# ADC_8CH.net
KiCad netlist of a schematic drawn in Altium Designer
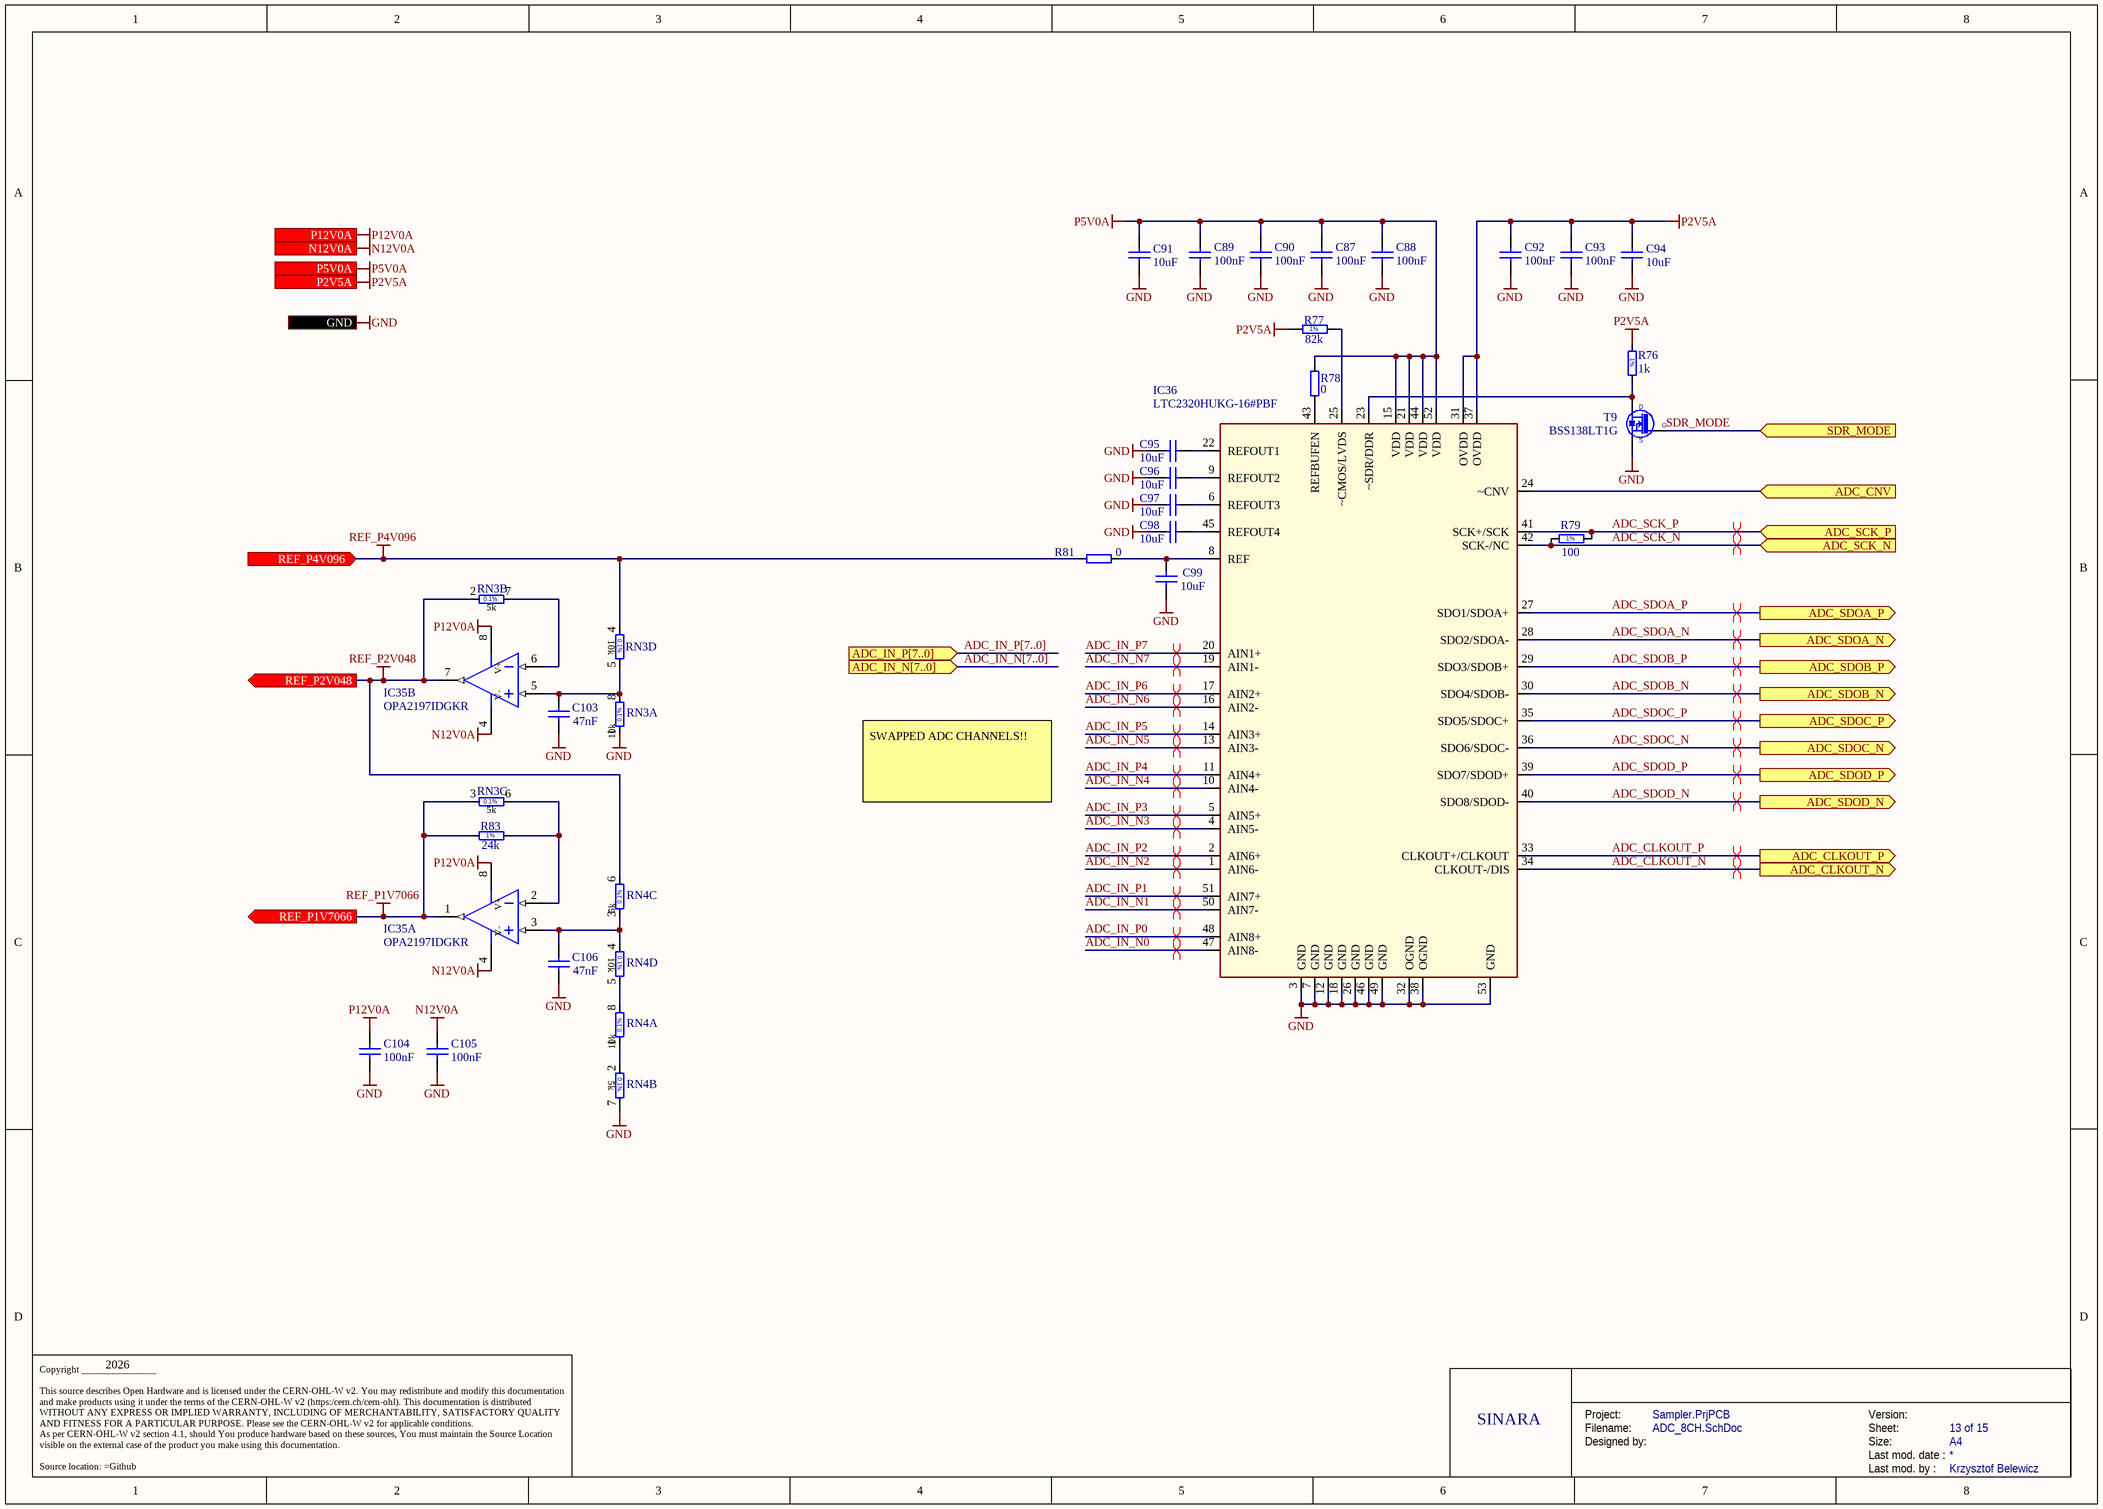
[diagram p0: ADC_8CH.SchDoc]

(export (version "E")
  (design (tool "Eeschema 10.0.6"))
  (components
    (comp (ref "C87")
      (value "100nF")
      (footprint "CAPC1005X55N")
      (description "Non-polarised capacitor")
      (fields
        (field (name "PART NUMBER") "CC0402_100NF_50V_10%_X7R")
        (field (name "VOLTAGE") "50V")
        (field (name "AUTHOR") "CERN DEM MR")
      )
      (libsource (lib "Capacitors") (part "Capacitor - non polarized"))
    )
    (comp (ref "C88")
      (value "100nF")
      (footprint "CAPC1005X55N")
      (description "Non-polarised capacitor")
      (fields
        (field (name "PART NUMBER") "CC0402_100NF_50V_10%_X7R")
        (field (name "VOLTAGE") "50V")
        (field (name "AUTHOR") "CERN DEM MR")
      )
      (libsource (lib "Capacitors") (part "Capacitor - non polarized"))
    )
    (comp (ref "C89")
      (value "100nF")
      (footprint "CAPC1005X55N")
      (description "Non-polarised capacitor")
      (fields
        (field (name "PART NUMBER") "CC0402_100NF_50V_10%_X7R")
        (field (name "VOLTAGE") "50V")
        (field (name "AUTHOR") "CERN DEM MR")
      )
      (libsource (lib "Capacitors") (part "Capacitor - non polarized"))
    )
    (comp (ref "C90")
      (value "100nF")
      (footprint "CAPC1005X55N")
      (description "Non-polarised capacitor")
      (fields
        (field (name "PART NUMBER") "CC0402_100NF_50V_10%_X7R")
        (field (name "VOLTAGE") "50V")
        (field (name "AUTHOR") "CERN DEM MR")
      )
      (libsource (lib "Capacitors") (part "Capacitor - non polarized"))
    )
    (comp (ref "C91")
      (value "10uF")
      (footprint "CAPC2012X95N")
      (description "Non-polarised capacitor")
      (fields
        (field (name "PART NUMBER") "CC0805_10UF_25V_10%_X5R")
        (field (name "VOLTAGE") "25V")
        (field (name "AUTHOR") "CERN DEM JLC")
      )
      (libsource (lib "Capacitors") (part "Capacitor - non polarized"))
    )
    (comp (ref "C92")
      (value "100nF")
      (footprint "CAPC1005X55N")
      (description "Non-polarised capacitor")
      (fields
        (field (name "PART NUMBER") "CC0402_100NF_50V_10%_X7R")
        (field (name "VOLTAGE") "50V")
        (field (name "AUTHOR") "CERN DEM MR")
      )
      (libsource (lib "Capacitors") (part "Capacitor - non polarized"))
    )
    (comp (ref "C93")
      (value "100nF")
      (footprint "CAPC1005X55N")
      (description "Non-polarised capacitor")
      (fields
        (field (name "PART NUMBER") "CC0402_100NF_50V_10%_X7R")
        (field (name "VOLTAGE") "50V")
        (field (name "AUTHOR") "CERN DEM MR")
      )
      (libsource (lib "Capacitors") (part "Capacitor - non polarized"))
    )
    (comp (ref "C94")
      (value "10uF")
      (footprint "CAPC2012X95N")
      (description "Non-polarised capacitor")
      (fields
        (field (name "PART NUMBER") "CC0805_10UF_25V_10%_X5R")
        (field (name "VOLTAGE") "25V")
        (field (name "AUTHOR") "CERN DEM JLC")
      )
      (libsource (lib "Capacitors") (part "Capacitor - non polarized"))
    )
    (comp (ref "C95")
      (value "10uF")
      (footprint "CAPC2012X95N")
      (description "Non-polarised capacitor")
      (fields
        (field (name "PART NUMBER") "CC0805_10UF_25V_10%_X5R")
        (field (name "VOLTAGE") "25V")
        (field (name "AUTHOR") "CERN DEM JLC")
      )
      (libsource (lib "Capacitors") (part "Capacitor - non polarized"))
    )
    (comp (ref "C96")
      (value "10uF")
      (footprint "CAPC2012X95N")
      (description "Non-polarised capacitor")
      (fields
        (field (name "PART NUMBER") "CC0805_10UF_25V_10%_X5R")
        (field (name "VOLTAGE") "25V")
        (field (name "AUTHOR") "CERN DEM JLC")
      )
      (libsource (lib "Capacitors") (part "Capacitor - non polarized"))
    )
    (comp (ref "C97")
      (value "10uF")
      (footprint "CAPC2012X95N")
      (description "Non-polarised capacitor")
      (fields
        (field (name "PART NUMBER") "CC0805_10UF_25V_10%_X5R")
        (field (name "VOLTAGE") "25V")
        (field (name "AUTHOR") "CERN DEM JLC")
      )
      (libsource (lib "Capacitors") (part "Capacitor - non polarized"))
    )
    (comp (ref "C98")
      (value "10uF")
      (footprint "CAPC2012X95N")
      (description "Non-polarised capacitor")
      (fields
        (field (name "PART NUMBER") "CC0805_10UF_25V_10%_X5R")
        (field (name "VOLTAGE") "25V")
        (field (name "AUTHOR") "CERN DEM JLC")
      )
      (libsource (lib "Capacitors") (part "Capacitor - non polarized"))
    )
    (comp (ref "C99")
      (value "10uF")
      (footprint "CAPC2012X95N")
      (description "Non-polarised capacitor")
      (fields
        (field (name "PART NUMBER") "CC0805_10UF_25V_10%_X5R")
        (field (name "VOLTAGE") "25V")
        (field (name "AUTHOR") "CERN DEM JLC")
      )
      (libsource (lib "Capacitors") (part "Capacitor - non polarized"))
    )
    (comp (ref "C103")
      (value "47nF")
      (footprint "CAPC2012X135N")
      (description "Non-polarised capacitor")
      (fields
        (field (name "PART NUMBER") "CC0805_47NF_25V_5%_C0G")
        (field (name "VOLTAGE") "25V")
        (field (name "AUTHOR") "CERN DEM JLC")
      )
      (libsource (lib "Capacitors") (part "Capacitor - non polarized"))
    )
    (comp (ref "C104")
      (value "100nF")
      (footprint "CAPC1005X55N")
      (description "Non-polarised capacitor")
      (fields
        (field (name "PART NUMBER") "CC0402_100NF_50V_10%_X7R")
        (field (name "VOLTAGE") "50V")
        (field (name "AUTHOR") "CERN DEM MR")
      )
      (libsource (lib "Capacitors") (part "Capacitor - non polarized"))
    )
    (comp (ref "C105")
      (value "100nF")
      (footprint "CAPC1005X55N")
      (description "Non-polarised capacitor")
      (fields
        (field (name "PART NUMBER") "CC0402_100NF_50V_10%_X7R")
        (field (name "VOLTAGE") "50V")
        (field (name "AUTHOR") "CERN DEM MR")
      )
      (libsource (lib "Capacitors") (part "Capacitor - non polarized"))
    )
    (comp (ref "C106")
      (value "47nF")
      (footprint "CAPC2012X135N")
      (description "Non-polarised capacitor")
      (fields
        (field (name "PART NUMBER") "CC0805_47NF_25V_5%_C0G")
        (field (name "VOLTAGE") "25V")
        (field (name "AUTHOR") "CERN DEM JLC")
      )
      (libsource (lib "Capacitors") (part "Capacitor - non polarized"))
    )
    (comp (ref "IC35")
      (value "OPA2197IDGKR")
      (footprint "SOP65P490X110-8N")
      (description "36-V, Precision, Rail-to-Rail Input Output, Low Offset Voltage Op Amp 8-VSSOP")
      (fields (field (name "MANUFACTURER") "TEXAS INSTRUMENTS") (field (name "AUTHOR") "GK"))
      (libsource (lib "LIBRARY_SCH") (part "OA_OPA2197IDGKR"))
    )
    (comp (ref "IC36")
      (value "LTC2320HUKG-16#PBF")
      (footprint "QFN50P700X800X80_HS-53M")
      (description "Octal, 16-Bit, 1.5Msps/Ch  Simultaneous Sampling ADC")
      (fields (field (name "MANUFACTURER") "LINEAR TECHNOLOGY") (field (name "AUTHOR") "GK"))
      (libsource (lib "LIBRARY_SCH") (part "ADC_LTC2320HUKG-16"))
    )
    (comp (ref "R76")
      (value "1k")
      (footprint "RESC1608X55N")
      (description "Resistor - 1%")
      (fields
        (field (name "PART NUMBER") "R0603_1K_1%_0.1W_100PPM")
        (field (name "POWER") "0.1W")
        (field (name "AUTHOR") "CERN DEM JLC")
      )
      (libsource (lib "Resistors") (part "Resistor - 1%"))
    )
    (comp (ref "R77")
      (value "82k")
      (footprint "RESC1608X55N")
      (description "Resistor - 1%")
      (fields
        (field (name "PART NUMBER") "R0603_82K_1%_0.1W_100PPM")
        (field (name "POWER") "0.1W")
        (field (name "AUTHOR") "CERN DEM JLC")
      )
      (libsource (lib "Resistors") (part "Resistor - 1%"))
    )
    (comp (ref "R78")
      (value "0")
      (footprint "RESC1005X40N")
      (description "Resistor")
      (fields
        (field (name "PART NUMBER") "R0402_0R_JUMPER")
        (field (name "MANUFACTURER") "GENERIC")
        (field (name "AUTHOR") "CERN DEM JLC")
      )
      (libsource (lib "Resistors") (part "Resistor"))
    )
    (comp (ref "R79")
      (value "100")
      (footprint "RESC1005X40N")
      (description "Resistor - 1%")
      (fields
        (field (name "PART NUMBER") "R0402_100R_1%_0.1W_100PPM")
        (field (name "POWER") "0.1W")
        (field (name "AUTHOR") "CERN DEM JLC")
      )
      (libsource (lib "Resistors") (part "Resistor - 1%"))
    )
    (comp (ref "R81")
      (value "0")
      (footprint "RESC1005X40N")
      (description "Resistor")
      (fields
        (field (name "PART NUMBER") "R0402_0R_JUMPER")
        (field (name "MANUFACTURER") "GENERIC")
        (field (name "AUTHOR") "CERN DEM JLC")
      )
      (libsource (lib "Resistors") (part "Resistor"))
    )
    (comp (ref "R83")
      (value "24k")
      (footprint "RESC1608X55N")
      (description "Resistor - 1%")
      (fields
        (field (name "PART NUMBER") "R0603_24K_1%_0.1W_100PPM")
        (field (name "POWER") "0.1W")
        (field (name "AUTHOR") "CERN DEM JLC")
      )
      (libsource (lib "Resistors") (part "Resistor - 1%"))
    )
    (comp (ref "RN3")
      (value "10k 5K 5K 10K")
      (footprint "SOIC127P600X175-8N")
      (description "DIL8 Resistor Network 4 Resistors 10k-5k-5k-10k 0.1%")
      (fields
        (field (name "PART NUMBER") "RN_10K_5K_VISHAY_AORN2-1AT3")
        (field (name "POWER") "4x0.1W")
        (field (name "AUTHOR") "CERN DEM JLC")
      )
      (libsource (lib "Resistors") (part "RN DIL8_4xR_10k-5k-5k-10k_0.1%"))
    )
    (comp (ref "RN4")
      (value "10k 5K 5K 10K")
      (footprint "SOIC127P600X175-8N")
      (description "DIL8 Resistor Network 4 Resistors 10k-5k-5k-10k 0.1%")
      (fields
        (field (name "PART NUMBER") "RN_10K_5K_VISHAY_AORN2-1AT3")
        (field (name "POWER") "4x0.1W")
        (field (name "AUTHOR") "CERN DEM JLC")
      )
      (libsource (lib "Resistors") (part "RN DIL8_4xR_10k-5k-5k-10k_0.1%"))
    )
    (comp (ref "T9")
      (value "BSS138LT1G")
      (footprint "SOT95P240X110-3N")
      (description "N-CHANNEL MOSFET WITH DIODE")
      (fields (field (name "MANUFACTURER") "ON SEMICONDUCTOR") (field (name "AUTHOR") "CERN DEM JLC"))
      (libsource (lib "ICs And Semiconductors") (part "N-MOSFET-D 1G 2S 3D"))
    )
  )
  (nets
    (net (code "1") (name "/ADC_CLKOUT_N") (class "Default")
      (node (ref "IC36") (pin "34") (pinfunction "CLKOUT-/DIS_34") (pintype "passive"))
    )
    (net (code "2") (name "/ADC_CLKOUT_P") (class "Default")
      (node (ref "IC36") (pin "33") (pinfunction "CLKOUT+/CLKOUT_33") (pintype "passive"))
    )
    (net (code "3") (name "/ADC_CNV") (class "Default")
      (node (ref "IC36") (pin "24") (pinfunction "~CNV_24") (pintype "passive"))
    )
    (net (code "4") (name "/ADC_IN_N0") (class "Default")
      (node (ref "IC36") (pin "47") (pinfunction "AIN8-_47") (pintype "passive"))
    )
    (net (code "5") (name "/ADC_IN_N1") (class "Default")
      (node (ref "IC36") (pin "50") (pinfunction "AIN7-_50") (pintype "passive"))
    )
    (net (code "6") (name "/ADC_IN_N2") (class "Default")
      (node (ref "IC36") (pin "1") (pinfunction "AIN6-_1") (pintype "passive"))
    )
    (net (code "7") (name "/ADC_IN_N3") (class "Default")
      (node (ref "IC36") (pin "4") (pinfunction "AIN5-_4") (pintype "passive"))
    )
    (net (code "8") (name "/ADC_IN_N4") (class "Default")
      (node (ref "IC36") (pin "10") (pinfunction "AIN4-_10") (pintype "passive"))
    )
    (net (code "9") (name "/ADC_IN_N5") (class "Default")
      (node (ref "IC36") (pin "13") (pinfunction "AIN3-_13") (pintype "passive"))
    )
    (net (code "10") (name "/ADC_IN_N6") (class "Default")
      (node (ref "IC36") (pin "16") (pinfunction "AIN2-_16") (pintype "passive"))
    )
    (net (code "11") (name "/ADC_IN_N7") (class "Default")
      (node (ref "IC36") (pin "19") (pinfunction "AIN1-_19") (pintype "passive"))
    )
    (net (code "13") (name "/ADC_IN_P0") (class "Default")
      (node (ref "IC36") (pin "48") (pinfunction "AIN8+_48") (pintype "passive"))
    )
    (net (code "14") (name "/ADC_IN_P1") (class "Default")
      (node (ref "IC36") (pin "51") (pinfunction "AIN7+_51") (pintype "passive"))
    )
    (net (code "15") (name "/ADC_IN_P2") (class "Default")
      (node (ref "IC36") (pin "2") (pinfunction "AIN6+_2") (pintype "passive"))
    )
    (net (code "16") (name "/ADC_IN_P3") (class "Default")
      (node (ref "IC36") (pin "5") (pinfunction "AIN5+_5") (pintype "passive"))
    )
    (net (code "17") (name "/ADC_IN_P4") (class "Default")
      (node (ref "IC36") (pin "11") (pinfunction "AIN4+_11") (pintype "passive"))
    )
    (net (code "18") (name "/ADC_IN_P5") (class "Default")
      (node (ref "IC36") (pin "14") (pinfunction "AIN3+_14") (pintype "passive"))
    )
    (net (code "19") (name "/ADC_IN_P6") (class "Default")
      (node (ref "IC36") (pin "17") (pinfunction "AIN2+_17") (pintype "passive"))
    )
    (net (code "20") (name "/ADC_IN_P7") (class "Default")
      (node (ref "IC36") (pin "20") (pinfunction "AIN1+_20") (pintype "passive"))
    )
    (net (code "22") (name "/ADC_SCK_N") (class "Default")
      (node (ref "IC36") (pin "42") (pinfunction "SCK-/NC_42") (pintype "passive"))
      (node (ref "R79") (pin "1") (pinfunction "1_1") (pintype "passive"))
    )
    (net (code "23") (name "/ADC_SCK_P") (class "Default")
      (node (ref "IC36") (pin "41") (pinfunction "SCK+/SCK_41") (pintype "passive"))
      (node (ref "R79") (pin "2") (pinfunction "2_2") (pintype "passive"))
    )
    (net (code "24") (name "/ADC_SDOA_N") (class "Default")
      (node (ref "IC36") (pin "28") (pinfunction "SDO2/SDOA-_28") (pintype "passive"))
    )
    (net (code "25") (name "/ADC_SDOA_P") (class "Default")
      (node (ref "IC36") (pin "27") (pinfunction "SDO1/SDOA+_27") (pintype "passive"))
    )
    (net (code "26") (name "/ADC_SDOB_N") (class "Default")
      (node (ref "IC36") (pin "30") (pinfunction "SDO4/SDOB-_30") (pintype "passive"))
    )
    (net (code "27") (name "/ADC_SDOB_P") (class "Default")
      (node (ref "IC36") (pin "29") (pinfunction "SDO3/SDOB+_29") (pintype "passive"))
    )
    (net (code "28") (name "/ADC_SDOC_N") (class "Default")
      (node (ref "IC36") (pin "36") (pinfunction "SDO6/SDOC-_36") (pintype "passive"))
    )
    (net (code "29") (name "/ADC_SDOC_P") (class "Default")
      (node (ref "IC36") (pin "35") (pinfunction "SDO5/SDOC+_35") (pintype "passive"))
    )
    (net (code "30") (name "/ADC_SDOD_N") (class "Default")
      (node (ref "IC36") (pin "40") (pinfunction "SDO8/SDOD-_40") (pintype "passive"))
    )
    (net (code "31") (name "/ADC_SDOD_P") (class "Default")
      (node (ref "IC36") (pin "39") (pinfunction "SDO7/SDOD+_39") (pintype "passive"))
    )
    (net (code "32") (name "/SDR_MODE") (class "Default")
      (node (ref "T9") (pin "1") (pinfunction "G_1") (pintype "passive"))
    )
    (net (code "33") (name "GND") (class "Default")
      (node (ref "C103") (pin "1") (pinfunction "1_1") (pintype "passive"))
      (node (ref "C104") (pin "1") (pinfunction "1_1") (pintype "passive"))
      (node (ref "C105") (pin "1") (pinfunction "1_1") (pintype "passive"))
      (node (ref "C106") (pin "1") (pinfunction "1_1") (pintype "passive"))
      (node (ref "C87") (pin "1") (pinfunction "1_1") (pintype "passive"))
      (node (ref "C88") (pin "1") (pinfunction "1_1") (pintype "passive"))
      (node (ref "C89") (pin "1") (pinfunction "1_1") (pintype "passive"))
      (node (ref "C90") (pin "1") (pinfunction "1_1") (pintype "passive"))
      (node (ref "C91") (pin "1") (pinfunction "1_1") (pintype "passive"))
      (node (ref "C92") (pin "1") (pinfunction "1_1") (pintype "passive"))
      (node (ref "C93") (pin "1") (pinfunction "1_1") (pintype "passive"))
      (node (ref "C94") (pin "1") (pinfunction "1_1") (pintype "passive"))
      (node (ref "C95") (pin "1") (pinfunction "1_1") (pintype "passive"))
      (node (ref "C96") (pin "1") (pinfunction "1_1") (pintype "passive"))
      (node (ref "C97") (pin "1") (pinfunction "1_1") (pintype "passive"))
      (node (ref "C98") (pin "1") (pinfunction "1_1") (pintype "passive"))
      (node (ref "C99") (pin "1") (pinfunction "1_1") (pintype "passive"))
      (node (ref "IC36") (pin "12") (pinfunction "GND_12") (pintype "passive"))
      (node (ref "IC36") (pin "18") (pinfunction "GND_18") (pintype "passive"))
      (node (ref "IC36") (pin "26") (pinfunction "GND_26") (pintype "passive"))
      (node (ref "IC36") (pin "3") (pinfunction "GND_3") (pintype "passive"))
      (node (ref "IC36") (pin "32") (pinfunction "OGND_32") (pintype "passive"))
      (node (ref "IC36") (pin "38") (pinfunction "OGND_38") (pintype "passive"))
      (node (ref "IC36") (pin "46") (pinfunction "GND_46") (pintype "passive"))
      (node (ref "IC36") (pin "49") (pinfunction "GND_49") (pintype "passive"))
      (node (ref "IC36") (pin "53") (pinfunction "GND_53") (pintype "passive"))
      (node (ref "IC36") (pin "7") (pinfunction "GND_7") (pintype "passive"))
      (node (ref "RN3") (pin "1") (pinfunction "1_1") (pintype "passive"))
      (node (ref "RN4") (pin "7") (pinfunction "7_7") (pintype "passive"))
      (node (ref "T9") (pin "2") (pinfunction "S_2") (pintype "passive"))
    )
    (net (code "34") (name "N12V0A") (class "Default")
      (node (ref "C105") (pin "2") (pinfunction "2_2") (pintype "passive"))
      (node (ref "IC35") (pin "4") (pinfunction "V-_4") (pintype "power_in"))
    )
    (net (code "35") (name "Net-(IC35A-IN+)") (class "Default")
      (node (ref "C106") (pin "2") (pinfunction "2_2") (pintype "passive"))
      (node (ref "IC35") (pin "3") (pinfunction "IN+_3") (pintype "input"))
      (node (ref "RN4") (pin "3") (pinfunction "3_3") (pintype "passive"))
      (node (ref "RN4") (pin "4") (pinfunction "4_4") (pintype "passive"))
    )
    (net (code "36") (name "Net-(IC35A-IN-)") (class "Default")
      (node (ref "IC35") (pin "2") (pinfunction "IN-_2") (pintype "input"))
      (node (ref "R83") (pin "1") (pinfunction "1_1") (pintype "passive"))
      (node (ref "RN3") (pin "6") (pinfunction "6_6") (pintype "passive"))
    )
    (net (code "37") (name "Net-(IC35B-IN+)") (class "Default")
      (node (ref "C103") (pin "2") (pinfunction "2_2") (pintype "passive"))
      (node (ref "IC35") (pin "5") (pinfunction "IN+_5") (pintype "input"))
      (node (ref "RN3") (pin "5") (pinfunction "5_5") (pintype "passive"))
      (node (ref "RN3") (pin "8") (pinfunction "8_8") (pintype "passive"))
    )
    (net (code "38") (name "Net-(IC35B-IN-)") (class "Default")
      (node (ref "IC35") (pin "6") (pinfunction "IN-_6") (pintype "input"))
      (node (ref "RN3") (pin "7") (pinfunction "7_7") (pintype "passive"))
    )
    (net (code "39") (name "Net-(IC36-REF)") (class "Default")
      (node (ref "C99") (pin "2") (pinfunction "2_2") (pintype "passive"))
      (node (ref "IC36") (pin "8") (pinfunction "REF_8") (pintype "passive"))
      (node (ref "R81") (pin "2") (pinfunction "2_2") (pintype "passive"))
    )
    (net (code "40") (name "Net-(IC36-REFBUFEN)") (class "Default")
      (node (ref "IC36") (pin "43") (pinfunction "REFBUFEN_43") (pintype "passive"))
      (node (ref "R78") (pin "1") (pinfunction "1_1") (pintype "passive"))
    )
    (net (code "41") (name "Net-(IC36-REFOUT1)") (class "Default")
      (node (ref "C95") (pin "2") (pinfunction "2_2") (pintype "passive"))
      (node (ref "IC36") (pin "22") (pinfunction "REFOUT1_22") (pintype "passive"))
    )
    (net (code "42") (name "Net-(IC36-REFOUT2)") (class "Default")
      (node (ref "C96") (pin "2") (pinfunction "2_2") (pintype "passive"))
      (node (ref "IC36") (pin "9") (pinfunction "REFOUT2_9") (pintype "passive"))
    )
    (net (code "43") (name "Net-(IC36-REFOUT3)") (class "Default")
      (node (ref "C97") (pin "2") (pinfunction "2_2") (pintype "passive"))
      (node (ref "IC36") (pin "6") (pinfunction "REFOUT3_6") (pintype "passive"))
    )
    (net (code "44") (name "Net-(IC36-REFOUT4)") (class "Default")
      (node (ref "C98") (pin "2") (pinfunction "2_2") (pintype "passive"))
      (node (ref "IC36") (pin "45") (pinfunction "REFOUT4_45") (pintype "passive"))
    )
    (net (code "45") (name "Net-(IC36-~CMOS{slash}LVDS)") (class "Default")
      (node (ref "IC36") (pin "25") (pinfunction "~CMOS/LVDS_25") (pintype "passive"))
      (node (ref "R77") (pin "2") (pinfunction "2_2") (pintype "passive"))
    )
    (net (code "46") (name "Net-(IC36-~SDR{slash}DDR)") (class "Default")
      (node (ref "IC36") (pin "23") (pinfunction "~SDR/DDR_23") (pintype "passive"))
      (node (ref "R76") (pin "2") (pinfunction "2_2") (pintype "passive"))
      (node (ref "T9") (pin "3") (pinfunction "D_3") (pintype "passive"))
    )
    (net (code "47") (name "Net-(RN4-Pad1)") (class "Default")
      (node (ref "RN4") (pin "1") (pinfunction "1_1") (pintype "passive"))
      (node (ref "RN4") (pin "2") (pinfunction "2_2") (pintype "passive"))
    )
    (net (code "48") (name "Net-(RN4-Pad5)") (class "Default")
      (node (ref "RN4") (pin "5") (pinfunction "5_5") (pintype "passive"))
      (node (ref "RN4") (pin "8") (pinfunction "8_8") (pintype "passive"))
    )
    (net (code "49") (name "P2V5A") (class "Default")
      (node (ref "C92") (pin "2") (pinfunction "2_2") (pintype "passive"))
      (node (ref "C93") (pin "2") (pinfunction "2_2") (pintype "passive"))
      (node (ref "C94") (pin "2") (pinfunction "2_2") (pintype "passive"))
      (node (ref "IC36") (pin "31") (pinfunction "OVDD_31") (pintype "passive"))
      (node (ref "IC36") (pin "37") (pinfunction "OVDD_37") (pintype "passive"))
      (node (ref "R76") (pin "1") (pinfunction "1_1") (pintype "passive"))
      (node (ref "R77") (pin "1") (pinfunction "1_1") (pintype "passive"))
    )
    (net (code "50") (name "P5V0A") (class "Default")
      (node (ref "C87") (pin "2") (pinfunction "2_2") (pintype "passive"))
      (node (ref "C88") (pin "2") (pinfunction "2_2") (pintype "passive"))
      (node (ref "C89") (pin "2") (pinfunction "2_2") (pintype "passive"))
      (node (ref "C90") (pin "2") (pinfunction "2_2") (pintype "passive"))
      (node (ref "C91") (pin "2") (pinfunction "2_2") (pintype "passive"))
      (node (ref "IC36") (pin "15") (pinfunction "VDD_15") (pintype "passive"))
      (node (ref "IC36") (pin "21") (pinfunction "VDD_21") (pintype "passive"))
      (node (ref "IC36") (pin "44") (pinfunction "VDD_44") (pintype "passive"))
      (node (ref "IC36") (pin "52") (pinfunction "VDD_52") (pintype "passive"))
      (node (ref "R78") (pin "2") (pinfunction "2_2") (pintype "passive"))
    )
    (net (code "51") (name "P12V0A") (class "Default")
      (node (ref "C104") (pin "2") (pinfunction "2_2") (pintype "passive"))
      (node (ref "IC35") (pin "8") (pinfunction "V+_8") (pintype "power_in"))
    )
    (net (code "52") (name "REF_P1V7066") (class "Default")
      (node (ref "IC35") (pin "1") (pinfunction "OUT_1") (pintype "output"))
      (node (ref "R83") (pin "2") (pinfunction "2_2") (pintype "passive"))
      (node (ref "RN3") (pin "3") (pinfunction "3_3") (pintype "passive"))
    )
    (net (code "53") (name "REF_P2V048") (class "Default")
      (node (ref "IC35") (pin "7") (pinfunction "OUT_7") (pintype "output"))
      (node (ref "RN3") (pin "2") (pinfunction "2_2") (pintype "passive"))
      (node (ref "RN4") (pin "6") (pinfunction "6_6") (pintype "passive"))
    )
    (net (code "54") (name "REF_P4V096") (class "Default")
      (node (ref "R81") (pin "1") (pinfunction "1_1") (pintype "passive"))
      (node (ref "RN3") (pin "4") (pinfunction "4_4") (pintype "passive"))
    )
  )
)
